# -.net
KiCad netlist of a schematic drawn in Altium Designer
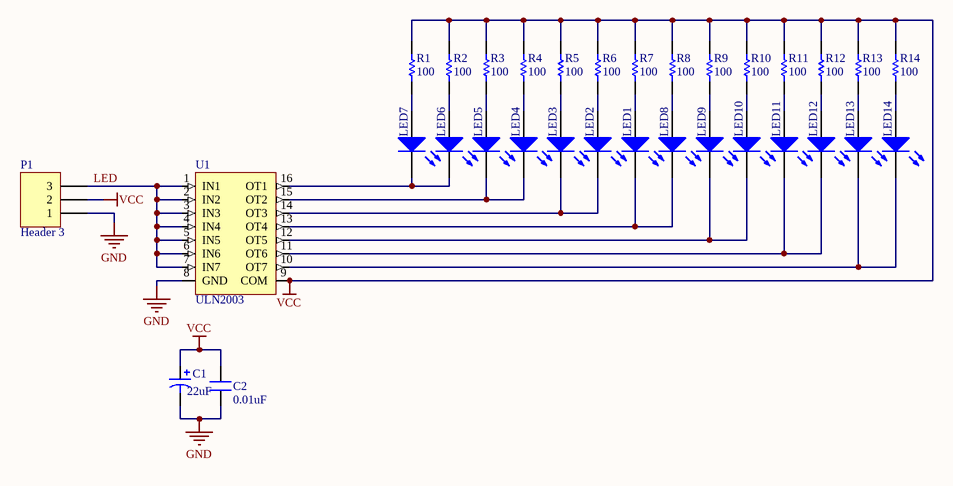
[diagram p0: 智能家居-电灯.SchDoc]

(export (version "E")
  (design (tool "Eeschema 10.0.6"))
  (components
    (comp (ref "C1")
      (value "22uF")
      (footprint "CD5")
      (description "Polarized Capacitor (Radial)")
      (fields (field (name "Comment") "Cap Pol1") (field (name "PUBLISHER") "Altium Limited"))
      (libsource (lib "Miscellaneous Devices") (part "Cap Pol1"))
    )
    (comp (ref "C2") (value "0.01uF") (footprint "0.1UF") (libsource (lib "WARSHIP") (part "C")))
    (comp (ref "LED1")
      (value "LED0")
      (footprint "LED-3")
      (description "Typical INFRARED GaAs LED")
      (fields (field (name "PUBLISHER") "Altium Limited"))
      (libsource (lib "Miscellaneous Devices") (part "LED0"))
    )
    (comp (ref "LED2")
      (value "LED0")
      (footprint "LED-3")
      (description "Typical INFRARED GaAs LED")
      (fields (field (name "PUBLISHER") "Altium Limited"))
      (libsource (lib "Miscellaneous Devices") (part "LED0"))
    )
    (comp (ref "LED3")
      (value "LED0")
      (footprint "LED-3")
      (description "Typical INFRARED GaAs LED")
      (fields (field (name "PUBLISHER") "Altium Limited"))
      (libsource (lib "Miscellaneous Devices") (part "LED0"))
    )
    (comp (ref "LED4")
      (value "LED0")
      (footprint "LED-3")
      (description "Typical INFRARED GaAs LED")
      (fields (field (name "PUBLISHER") "Altium Limited"))
      (libsource (lib "Miscellaneous Devices") (part "LED0"))
    )
    (comp (ref "LED5")
      (value "LED0")
      (footprint "LED-3")
      (description "Typical INFRARED GaAs LED")
      (fields (field (name "PUBLISHER") "Altium Limited"))
      (libsource (lib "Miscellaneous Devices") (part "LED0"))
    )
    (comp (ref "LED6")
      (value "LED0")
      (footprint "LED-3")
      (description "Typical INFRARED GaAs LED")
      (fields (field (name "PUBLISHER") "Altium Limited"))
      (libsource (lib "Miscellaneous Devices") (part "LED0"))
    )
    (comp (ref "LED7")
      (value "LED0")
      (footprint "LED-3")
      (description "Typical INFRARED GaAs LED")
      (fields (field (name "PUBLISHER") "Altium Limited"))
      (libsource (lib "Miscellaneous Devices") (part "LED0"))
    )
    (comp (ref "LED8")
      (value "LED0")
      (footprint "LED-3")
      (description "Typical INFRARED GaAs LED")
      (fields (field (name "PUBLISHER") "Altium Limited"))
      (libsource (lib "Miscellaneous Devices") (part "LED0"))
    )
    (comp (ref "LED9")
      (value "LED0")
      (footprint "LED-3")
      (description "Typical INFRARED GaAs LED")
      (fields (field (name "PUBLISHER") "Altium Limited"))
      (libsource (lib "Miscellaneous Devices") (part "LED0"))
    )
    (comp (ref "LED10")
      (value "LED0")
      (footprint "LED-3")
      (description "Typical INFRARED GaAs LED")
      (fields (field (name "PUBLISHER") "Altium Limited"))
      (libsource (lib "Miscellaneous Devices") (part "LED0"))
    )
    (comp (ref "LED11")
      (value "LED0")
      (footprint "LED-3")
      (description "Typical INFRARED GaAs LED")
      (fields (field (name "PUBLISHER") "Altium Limited"))
      (libsource (lib "Miscellaneous Devices") (part "LED0"))
    )
    (comp (ref "LED12")
      (value "LED0")
      (footprint "LED-3")
      (description "Typical INFRARED GaAs LED")
      (fields (field (name "PUBLISHER") "Altium Limited"))
      (libsource (lib "Miscellaneous Devices") (part "LED0"))
    )
    (comp (ref "LED13")
      (value "LED0")
      (footprint "LED-3")
      (description "Typical INFRARED GaAs LED")
      (fields (field (name "PUBLISHER") "Altium Limited"))
      (libsource (lib "Miscellaneous Devices") (part "LED0"))
    )
    (comp (ref "LED14")
      (value "LED0")
      (footprint "LED-3")
      (description "Typical INFRARED GaAs LED")
      (fields (field (name "PUBLISHER") "Altium Limited"))
      (libsource (lib "Miscellaneous Devices") (part "LED0"))
    )
    (comp (ref "P1")
      (value "Header 3")
      (footprint "TJC3-3A")
      (description "Header, 3-Pin")
      (fields (field (name "PUBLISHER") "Altium Limited"))
      (libsource (lib "Miscellaneous Connectors") (part "Header 3"))
    )
    (comp (ref "R1")
      (value "100")
      (footprint "AXIAL-0.3")
      (description "Resistor")
      (fields (field (name "Comment") "Res1") (field (name "PUBLISHER") "Altium Limited"))
      (libsource (lib "Miscellaneous Devices") (part "Res1"))
    )
    (comp (ref "R2")
      (value "100")
      (footprint "AXIAL-0.3")
      (description "Resistor")
      (fields (field (name "Comment") "Res1") (field (name "PUBLISHER") "Altium Limited"))
      (libsource (lib "Miscellaneous Devices") (part "Res1"))
    )
    (comp (ref "R3")
      (value "100")
      (footprint "AXIAL-0.3")
      (description "Resistor")
      (fields (field (name "Comment") "Res1") (field (name "PUBLISHER") "Altium Limited"))
      (libsource (lib "Miscellaneous Devices") (part "Res1"))
    )
    (comp (ref "R4")
      (value "100")
      (footprint "AXIAL-0.3")
      (description "Resistor")
      (fields (field (name "Comment") "Res1") (field (name "PUBLISHER") "Altium Limited"))
      (libsource (lib "Miscellaneous Devices") (part "Res1"))
    )
    (comp (ref "R5")
      (value "100")
      (footprint "AXIAL-0.3")
      (description "Resistor")
      (fields (field (name "Comment") "Res1") (field (name "PUBLISHER") "Altium Limited"))
      (libsource (lib "Miscellaneous Devices") (part "Res1"))
    )
    (comp (ref "R6")
      (value "100")
      (footprint "AXIAL-0.3")
      (description "Resistor")
      (fields (field (name "Comment") "Res1") (field (name "PUBLISHER") "Altium Limited"))
      (libsource (lib "Miscellaneous Devices") (part "Res1"))
    )
    (comp (ref "R7")
      (value "100")
      (footprint "AXIAL-0.3")
      (description "Resistor")
      (fields (field (name "Comment") "Res1") (field (name "PUBLISHER") "Altium Limited"))
      (libsource (lib "Miscellaneous Devices") (part "Res1"))
    )
    (comp (ref "R8")
      (value "100")
      (footprint "AXIAL-0.3")
      (description "Resistor")
      (fields (field (name "Comment") "Res1") (field (name "PUBLISHER") "Altium Limited"))
      (libsource (lib "Miscellaneous Devices") (part "Res1"))
    )
    (comp (ref "R9")
      (value "100")
      (footprint "AXIAL-0.3")
      (description "Resistor")
      (fields (field (name "Comment") "Res1") (field (name "PUBLISHER") "Altium Limited"))
      (libsource (lib "Miscellaneous Devices") (part "Res1"))
    )
    (comp (ref "R10")
      (value "100")
      (footprint "AXIAL-0.3")
      (description "Resistor")
      (fields (field (name "Comment") "Res1") (field (name "PUBLISHER") "Altium Limited"))
      (libsource (lib "Miscellaneous Devices") (part "Res1"))
    )
    (comp (ref "R11")
      (value "100")
      (footprint "AXIAL-0.3")
      (description "Resistor")
      (fields (field (name "Comment") "Res1") (field (name "PUBLISHER") "Altium Limited"))
      (libsource (lib "Miscellaneous Devices") (part "Res1"))
    )
    (comp (ref "R12")
      (value "100")
      (footprint "AXIAL-0.3")
      (description "Resistor")
      (fields (field (name "Comment") "Res1") (field (name "PUBLISHER") "Altium Limited"))
      (libsource (lib "Miscellaneous Devices") (part "Res1"))
    )
    (comp (ref "R13")
      (value "100")
      (footprint "AXIAL-0.3")
      (description "Resistor")
      (fields (field (name "Comment") "Res1") (field (name "PUBLISHER") "Altium Limited"))
      (libsource (lib "Miscellaneous Devices") (part "Res1"))
    )
    (comp (ref "R14")
      (value "100")
      (footprint "AXIAL-0.3")
      (description "Resistor")
      (fields (field (name "Comment") "Res1") (field (name "PUBLISHER") "Altium Limited"))
      (libsource (lib "Miscellaneous Devices") (part "Res1"))
    )
    (comp (ref "U1") (value "ULN2003") (footprint "DIP16") (libsource (lib "杂项库") (part "ULN2003")))
  )
  (nets
    (net (code "1") (name "/LED") (class "Default")
      (node (ref "P1") (pin "3") (pinfunction "3_3") (pintype "passive"))
      (node (ref "U1") (pin "1") (pinfunction "IN1_1") (pintype "input"))
      (node (ref "U1") (pin "2") (pinfunction "IN2_2") (pintype "input"))
      (node (ref "U1") (pin "3") (pinfunction "IN3_3") (pintype "input"))
      (node (ref "U1") (pin "4") (pinfunction "IN4_4") (pintype "input"))
      (node (ref "U1") (pin "5") (pinfunction "IN5_5") (pintype "input"))
      (node (ref "U1") (pin "6") (pinfunction "IN6_6") (pintype "input"))
      (node (ref "U1") (pin "7") (pinfunction "IN7_7") (pintype "input"))
    )
    (net (code "2") (name "GND") (class "Default")
      (node (ref "C1") (pin "2") (pinfunction "2_2") (pintype "passive"))
      (node (ref "C2") (pin "1") (pintype "passive"))
      (node (ref "P1") (pin "1") (pinfunction "1_1") (pintype "passive"))
      (node (ref "U1") (pin "8") (pinfunction "GND_8") (pintype "power_in"))
    )
    (net (code "3") (name "Net-(LED1-A)") (class "Default")
      (node (ref "LED1") (pin "1") (pinfunction "A_1") (pintype "passive"))
      (node (ref "R7") (pin "1") (pinfunction "1_1") (pintype "passive"))
    )
    (net (code "4") (name "Net-(LED1-K)") (class "Default")
      (node (ref "LED1") (pin "2") (pinfunction "K_2") (pintype "passive"))
      (node (ref "LED8") (pin "2") (pinfunction "K_2") (pintype "passive"))
      (node (ref "U1") (pin "13") (pinfunction "OT4_13") (pintype "output"))
    )
    (net (code "5") (name "Net-(LED2-A)") (class "Default")
      (node (ref "LED2") (pin "1") (pinfunction "A_1") (pintype "passive"))
      (node (ref "R6") (pin "1") (pinfunction "1_1") (pintype "passive"))
    )
    (net (code "6") (name "Net-(LED2-K)") (class "Default")
      (node (ref "LED2") (pin "2") (pinfunction "K_2") (pintype "passive"))
      (node (ref "LED3") (pin "2") (pinfunction "K_2") (pintype "passive"))
      (node (ref "U1") (pin "14") (pinfunction "OT3_14") (pintype "output"))
    )
    (net (code "7") (name "Net-(LED3-A)") (class "Default")
      (node (ref "LED3") (pin "1") (pinfunction "A_1") (pintype "passive"))
      (node (ref "R5") (pin "1") (pinfunction "1_1") (pintype "passive"))
    )
    (net (code "8") (name "Net-(LED4-A)") (class "Default")
      (node (ref "LED4") (pin "1") (pinfunction "A_1") (pintype "passive"))
      (node (ref "R4") (pin "1") (pinfunction "1_1") (pintype "passive"))
    )
    (net (code "9") (name "Net-(LED4-K)") (class "Default")
      (node (ref "LED4") (pin "2") (pinfunction "K_2") (pintype "passive"))
      (node (ref "LED5") (pin "2") (pinfunction "K_2") (pintype "passive"))
      (node (ref "U1") (pin "15") (pinfunction "OT2_15") (pintype "output"))
    )
    (net (code "10") (name "Net-(LED5-A)") (class "Default")
      (node (ref "LED5") (pin "1") (pinfunction "A_1") (pintype "passive"))
      (node (ref "R3") (pin "1") (pinfunction "1_1") (pintype "passive"))
    )
    (net (code "11") (name "Net-(LED6-A)") (class "Default")
      (node (ref "LED6") (pin "1") (pinfunction "A_1") (pintype "passive"))
      (node (ref "R2") (pin "1") (pinfunction "1_1") (pintype "passive"))
    )
    (net (code "12") (name "Net-(LED6-K)") (class "Default")
      (node (ref "LED6") (pin "2") (pinfunction "K_2") (pintype "passive"))
      (node (ref "LED7") (pin "2") (pinfunction "K_2") (pintype "passive"))
      (node (ref "U1") (pin "16") (pinfunction "OT1_16") (pintype "output"))
    )
    (net (code "13") (name "Net-(LED7-A)") (class "Default")
      (node (ref "LED7") (pin "1") (pinfunction "A_1") (pintype "passive"))
      (node (ref "R1") (pin "1") (pinfunction "1_1") (pintype "passive"))
    )
    (net (code "14") (name "Net-(LED8-A)") (class "Default")
      (node (ref "LED8") (pin "1") (pinfunction "A_1") (pintype "passive"))
      (node (ref "R8") (pin "1") (pinfunction "1_1") (pintype "passive"))
    )
    (net (code "15") (name "Net-(LED9-A)") (class "Default")
      (node (ref "LED9") (pin "1") (pinfunction "A_1") (pintype "passive"))
      (node (ref "R9") (pin "1") (pinfunction "1_1") (pintype "passive"))
    )
    (net (code "16") (name "Net-(LED10-A)") (class "Default")
      (node (ref "LED10") (pin "1") (pinfunction "A_1") (pintype "passive"))
      (node (ref "R10") (pin "1") (pinfunction "1_1") (pintype "passive"))
    )
    (net (code "17") (name "Net-(LED10-K)") (class "Default")
      (node (ref "LED10") (pin "2") (pinfunction "K_2") (pintype "passive"))
      (node (ref "LED9") (pin "2") (pinfunction "K_2") (pintype "passive"))
      (node (ref "U1") (pin "12") (pinfunction "OT5_12") (pintype "output"))
    )
    (net (code "18") (name "Net-(LED11-A)") (class "Default")
      (node (ref "LED11") (pin "1") (pinfunction "A_1") (pintype "passive"))
      (node (ref "R11") (pin "1") (pinfunction "1_1") (pintype "passive"))
    )
    (net (code "19") (name "Net-(LED11-K)") (class "Default")
      (node (ref "LED11") (pin "2") (pinfunction "K_2") (pintype "passive"))
      (node (ref "LED12") (pin "2") (pinfunction "K_2") (pintype "passive"))
      (node (ref "U1") (pin "11") (pinfunction "OT6_11") (pintype "output"))
    )
    (net (code "20") (name "Net-(LED12-A)") (class "Default")
      (node (ref "LED12") (pin "1") (pinfunction "A_1") (pintype "passive"))
      (node (ref "R12") (pin "1") (pinfunction "1_1") (pintype "passive"))
    )
    (net (code "21") (name "Net-(LED13-A)") (class "Default")
      (node (ref "LED13") (pin "1") (pinfunction "A_1") (pintype "passive"))
      (node (ref "R13") (pin "1") (pinfunction "1_1") (pintype "passive"))
    )
    (net (code "22") (name "Net-(LED13-K)") (class "Default")
      (node (ref "LED13") (pin "2") (pinfunction "K_2") (pintype "passive"))
      (node (ref "LED14") (pin "2") (pinfunction "K_2") (pintype "passive"))
      (node (ref "U1") (pin "10") (pinfunction "OT7_10") (pintype "output"))
    )
    (net (code "23") (name "Net-(LED14-A)") (class "Default")
      (node (ref "LED14") (pin "1") (pinfunction "A_1") (pintype "passive"))
      (node (ref "R14") (pin "1") (pinfunction "1_1") (pintype "passive"))
    )
    (net (code "24") (name "VCC") (class "Default")
      (node (ref "C1") (pin "1") (pinfunction "1_1") (pintype "passive"))
      (node (ref "C2") (pin "2") (pintype "passive"))
      (node (ref "P1") (pin "2") (pinfunction "2_2") (pintype "passive"))
      (node (ref "R1") (pin "2") (pinfunction "2_2") (pintype "passive"))
      (node (ref "R10") (pin "2") (pinfunction "2_2") (pintype "passive"))
      (node (ref "R11") (pin "2") (pinfunction "2_2") (pintype "passive"))
      (node (ref "R12") (pin "2") (pinfunction "2_2") (pintype "passive"))
      (node (ref "R13") (pin "2") (pinfunction "2_2") (pintype "passive"))
      (node (ref "R14") (pin "2") (pinfunction "2_2") (pintype "passive"))
      (node (ref "R2") (pin "2") (pinfunction "2_2") (pintype "passive"))
      (node (ref "R3") (pin "2") (pinfunction "2_2") (pintype "passive"))
      (node (ref "R4") (pin "2") (pinfunction "2_2") (pintype "passive"))
      (node (ref "R5") (pin "2") (pinfunction "2_2") (pintype "passive"))
      (node (ref "R6") (pin "2") (pinfunction "2_2") (pintype "passive"))
      (node (ref "R7") (pin "2") (pinfunction "2_2") (pintype "passive"))
      (node (ref "R8") (pin "2") (pinfunction "2_2") (pintype "passive"))
      (node (ref "R9") (pin "2") (pinfunction "2_2") (pintype "passive"))
      (node (ref "U1") (pin "9") (pinfunction "COM_9") (pintype "power_in"))
    )
  )
)
